# boomerang.net
KiCad netlist of a schematic drawn in EAGLE
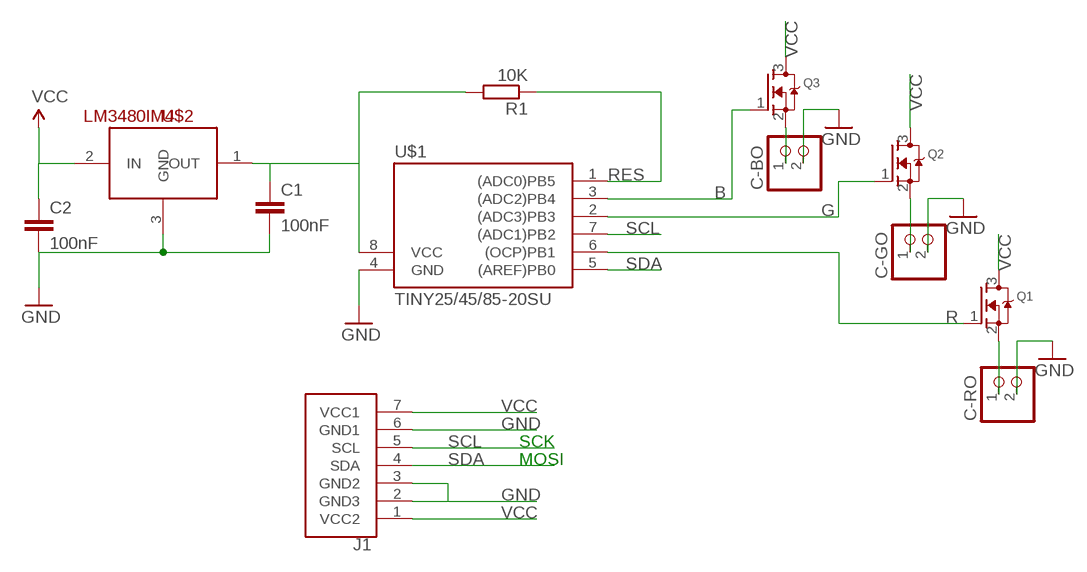
[diagram p0: schematic, sheet 1]

(export (version "E")
  (design (tool "Eeschema 10.0.6"))
  (components
    (comp (ref "C-BO")
      (value "PINHD-1X2M")
      (footprint "eagle-import:1X02M")
      (libsource (lib "eagle-import") (part "PINHD-1X2M"))
    )
    (comp (ref "C-GO")
      (value "PINHD-1X2M")
      (footprint "eagle-import:1X02M")
      (libsource (lib "eagle-import") (part "PINHD-1X2M"))
    )
    (comp (ref "C-RO")
      (value "PINHD-1X2M")
      (footprint "eagle-import:1X02M")
      (libsource (lib "eagle-import") (part "PINHD-1X2M"))
    )
    (comp (ref "C1")
      (value "100nF")
      (footprint "eagle-import:C0603")
      (libsource (lib "eagle-import") (part "C-EUC0603"))
    )
    (comp (ref "C2")
      (value "100nF")
      (footprint "eagle-import:C0603")
      (libsource (lib "eagle-import") (part "C-EUC0603"))
    )
    (comp (ref "J1")
      (value "SATA7-RA")
      (footprint "eagle-import:SATA7-RA")
      (libsource (lib "eagle-import") (part "SATA7-RA"))
    )
    (comp (ref "Q1")
      (value "MOSFET-NREFLOW")
      (footprint "eagle-import:SOT23")
      (libsource (lib "eagle-import") (part "MOSFET-NREFLOW"))
    )
    (comp (ref "Q2")
      (value "MOSFET-NREFLOW")
      (footprint "eagle-import:SOT23")
      (libsource (lib "eagle-import") (part "MOSFET-NREFLOW"))
    )
    (comp (ref "Q3")
      (value "MOSFET-NREFLOW")
      (footprint "eagle-import:SOT23")
      (libsource (lib "eagle-import") (part "MOSFET-NREFLOW"))
    )
    (comp (ref "R1")
      (value "10K")
      (footprint "eagle-import:R0603")
      (libsource (lib "eagle-import") (part "R-EU_R0603"))
    )
    (comp (ref "U$1")
      (value "TINY25/45/85-20SU")
      (footprint "eagle-import:SOIC8")
      (libsource (lib "eagle-import") (part "TINY25/45/85-20SU"))
    )
    (comp (ref "U$2")
      (value "LM3480IM4")
      (footprint "eagle-import:SOT23-3")
      (libsource (lib "eagle-import") (part "LM3480IM4"))
    )
  )
  (nets
    (net (code "1") (name "/B") (class "Default")
      (node (ref "Q3") (pin "1") (pinfunction "G_1") (pintype "bidirectional"))
      (node (ref "U$1") (pin "3") (pinfunction "(ADC2)PB4_3") (pintype "bidirectional"))
    )
    (net (code "2") (name "/G") (class "Default")
      (node (ref "Q2") (pin "1") (pinfunction "G_1") (pintype "bidirectional"))
      (node (ref "U$1") (pin "2") (pinfunction "(ADC3)PB3_2") (pintype "bidirectional"))
    )
    (net (code "3") (name "/R") (class "Default")
      (node (ref "Q1") (pin "1") (pinfunction "G_1") (pintype "bidirectional"))
      (node (ref "U$1") (pin "6") (pinfunction "(OCP)PB1_6") (pintype "bidirectional"))
    )
    (net (code "4") (name "/RES") (class "Default")
      (node (ref "R1") (pin "1") (pinfunction "1_1") (pintype "passive"))
      (node (ref "U$1") (pin "1") (pinfunction "(ADC0)PB5_1") (pintype "bidirectional"))
    )
    (net (code "5") (name "/SCL") (class "Default")
      (node (ref "J1") (pin "5") (pinfunction "SCL_5") (pintype "bidirectional"))
      (node (ref "U$1") (pin "7") (pinfunction "(ADC1)PB2_7") (pintype "bidirectional"))
    )
    (net (code "6") (name "/SDA") (class "Default")
      (node (ref "J1") (pin "4") (pinfunction "SDA_4") (pintype "bidirectional"))
      (node (ref "U$1") (pin "5") (pinfunction "(AREF)PB0_5") (pintype "bidirectional"))
    )
    (net (code "7") (name "GND") (class "Default")
      (node (ref "C-BO") (pin "2") (pinfunction "2_2") (pintype "passive"))
      (node (ref "C-GO") (pin "2") (pinfunction "2_2") (pintype "passive"))
      (node (ref "C-RO") (pin "2") (pinfunction "2_2") (pintype "passive"))
      (node (ref "C1") (pin "2") (pinfunction "2_2") (pintype "passive"))
      (node (ref "C2") (pin "2") (pinfunction "2_2") (pintype "passive"))
      (node (ref "J1") (pin "2") (pinfunction "GND3_2") (pintype "power_in"))
      (node (ref "J1") (pin "3") (pinfunction "GND2_3") (pintype "power_in"))
      (node (ref "J1") (pin "6") (pinfunction "GND1_6") (pintype "power_in"))
      (node (ref "U$1") (pin "4") (pinfunction "GND_4") (pintype "power_in"))
      (node (ref "U$2") (pin "3") (pinfunction "GND_3") (pintype "bidirectional"))
    )
    (net (code "8") (name "Net-(Q1-S)") (class "Default")
      (node (ref "C-RO") (pin "1") (pinfunction "1_1") (pintype "passive"))
      (node (ref "Q1") (pin "2") (pinfunction "S_2") (pintype "bidirectional"))
    )
    (net (code "9") (name "Net-(Q2-S)") (class "Default")
      (node (ref "C-GO") (pin "1") (pinfunction "1_1") (pintype "passive"))
      (node (ref "Q2") (pin "2") (pinfunction "S_2") (pintype "bidirectional"))
    )
    (net (code "10") (name "Net-(Q3-S)") (class "Default")
      (node (ref "C-BO") (pin "1") (pinfunction "1_1") (pintype "passive"))
      (node (ref "Q3") (pin "2") (pinfunction "S_2") (pintype "bidirectional"))
    )
    (net (code "11") (name "Net-(U$1-VCC)") (class "Default")
      (node (ref "C1") (pin "1") (pinfunction "1_1") (pintype "passive"))
      (node (ref "R1") (pin "2") (pinfunction "2_2") (pintype "passive"))
      (node (ref "U$1") (pin "8") (pinfunction "VCC_8") (pintype "power_in"))
      (node (ref "U$2") (pin "1") (pinfunction "OUT_1") (pintype "bidirectional"))
    )
    (net (code "12") (name "VCC") (class "Default")
      (node (ref "C2") (pin "1") (pinfunction "1_1") (pintype "passive"))
      (node (ref "J1") (pin "1") (pinfunction "VCC2_1") (pintype "power_in"))
      (node (ref "J1") (pin "7") (pinfunction "VCC1_7") (pintype "power_in"))
      (node (ref "Q1") (pin "3") (pinfunction "D_3") (pintype "bidirectional"))
      (node (ref "Q2") (pin "3") (pinfunction "D_3") (pintype "bidirectional"))
      (node (ref "Q3") (pin "3") (pinfunction "D_3") (pintype "bidirectional"))
      (node (ref "U$2") (pin "2") (pinfunction "IN_2") (pintype "bidirectional"))
    )
  )
)
